# tablo_tara.net
KiCad netlist of a schematic drawn in Altium Designer
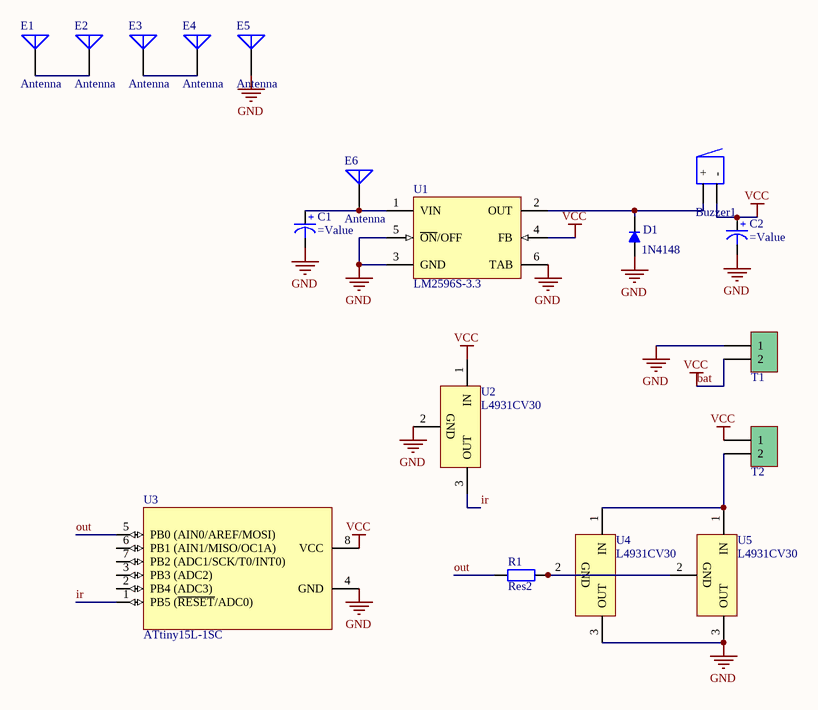
[diagram p0: tablo tara.SchDoc]

(export (version "E")
  (design (tool "Eeschema 10.0.6"))
  (components
    (comp (ref "Buzzer1")
      (value "Buzzer")
      (footprint "BUZZER")
      (fields (field (name "DESIGNER") "Seyed Mohsen Ghasemain"))
      (libsource (lib "PicPars.com_usefully_Library") (part "Buzzer"))
    )
    (comp (ref "C1")
      (value "~")
      (footprint "ELEC-CAP-RAD10-20")
      (description "Electrolytic Capacitor")
      (libsource (lib "AltiumLib1") (part "Capacitor Electrolytic"))
    )
    (comp (ref "C2")
      (value "~")
      (footprint "ELEC-CAP-RAD10-20")
      (description "Electrolytic Capacitor")
      (libsource (lib "AltiumLib1") (part "Capacitor Electrolytic"))
    )
    (comp (ref "D1")
      (value "MODEL")
      (footprint "DO-41")
      (description "Diode")
      (fields (field (name "MODEL") "1N4148"))
      (libsource (lib "AltiumLib1") (part "Diode"))
    )
    (comp (ref "E1")
      (value "Antenna")
      (footprint "PIN1")
      (description "Generic Antenna")
      (fields (field (name "PUBLISHER") "Altium Limited"))
      (libsource (lib "Miscellaneous Devices") (part "Antenna"))
    )
    (comp (ref "E2")
      (value "Antenna")
      (footprint "PIN1")
      (description "Generic Antenna")
      (fields (field (name "PUBLISHER") "Altium Limited"))
      (libsource (lib "Miscellaneous Devices") (part "Antenna"))
    )
    (comp (ref "E3")
      (value "Antenna")
      (footprint "PIN1")
      (description "Generic Antenna")
      (fields (field (name "PUBLISHER") "Altium Limited"))
      (libsource (lib "Miscellaneous Devices") (part "Antenna"))
    )
    (comp (ref "E4")
      (value "Antenna")
      (footprint "PIN1")
      (description "Generic Antenna")
      (fields (field (name "PUBLISHER") "Altium Limited"))
      (libsource (lib "Miscellaneous Devices") (part "Antenna"))
    )
    (comp (ref "E5")
      (value "Antenna")
      (footprint "PIN1")
      (description "Generic Antenna")
      (fields (field (name "PUBLISHER") "Altium Limited"))
      (libsource (lib "Miscellaneous Devices") (part "Antenna"))
    )
    (comp (ref "E6")
      (value "Antenna")
      (footprint "PIN1")
      (description "Generic Antenna")
      (fields (field (name "PUBLISHER") "Altium Limited"))
      (libsource (lib "Miscellaneous Devices") (part "Antenna"))
    )
    (comp (ref "R1")
      (value "Res2")
      (footprint "Res50")
      (description "Resistor")
      (fields (field (name "PUBLISHER") "Altium Limited"))
      (libsource (lib "Miscellaneous Devices") (part "Res50"))
    )
    (comp (ref "T1")
      (value "Phoenix terminal")
      (footprint "phoenix terminal 2")
      (description "Terminal 2 Pin")
      (fields (field (name "DESIGNER") "Seyed Mohsen Ghasemain") (field (name "E-MAIL") "picpars@gmail.com"))
      (libsource (lib "PicPars.com_usefully_Library") (part "Phoenix terminal 2"))
    )
    (comp (ref "T2")
      (value "Phoenix terminal")
      (footprint "phoenix terminal 2")
      (description "Terminal 2 Pin")
      (fields (field (name "DESIGNER") "Seyed Mohsen Ghasemain") (field (name "E-MAIL") "picpars@gmail.com"))
      (libsource (lib "PicPars.com_usefully_Library") (part "Phoenix terminal 2"))
    )
    (comp (ref "U1")
      (value "LM2596S-3.3")
      (footprint "TS5B_N")
      (description "SIMPLE SWITCHER Power Converter 150 KHz 3A Step-Down Voltage Regulator")
      (fields
        (field (name "MANUFACTURER") "National Semiconductor")
        (field (name "DIGIKEYPARTNUMBER") "LM2596S-3.3-ND")
        (field (name "PUBLISHER") "Altium Limited")
      )
      (libsource (lib "NSC Switcher") (part "LM2596S-3.3"))
    )
    (comp (ref "U2")
      (value "L4931CV30")
      (footprint "TO-220A")
      (description "250mA, Very Low Drop ( 0.4V) Voltage Regulator")
      (fields (field (name "PUBLISHER") "Altium Limited"))
      (libsource (lib "ST Power Mgt Voltage Regulator") (part "L4931CV30"))
    )
    (comp (ref "U3")
      (value "ATtiny15L-1SC")
      (footprint "8S2_N")
      (description "8-Bit AVR Microcontroller with 1K Byte of Flash Memory")
      (fields (field (name "PUBLISHER") "Altium Limited"))
      (libsource (lib "Atmel Microcontroller 8-Bit AVR") (part "ATtiny15L-1SC"))
    )
    (comp (ref "U4")
      (value "L4931CV30")
      (footprint "TO-220A")
      (description "250mA, Very Low Drop ( 0.4V) Voltage Regulator")
      (fields (field (name "PUBLISHER") "Altium Limited"))
      (libsource (lib "ST Power Mgt Voltage Regulator") (part "L4931CV30"))
    )
    (comp (ref "U5")
      (value "L4931CV30")
      (footprint "TO-220A")
      (description "250mA, Very Low Drop ( 0.4V) Voltage Regulator")
      (fields (field (name "PUBLISHER") "Altium Limited"))
      (libsource (lib "ST Power Mgt Voltage Regulator") (part "L4931CV30"))
    )
  )
  (nets
    (net (code "1") (name "/ir") (class "Default")
      (node (ref "U2") (pin "3") (pinfunction "OUT_3") (pintype "power_in"))
      (node (ref "U3") (pin "1") (pinfunction "PB5_(~{RESET}/ADC0)_1") (pintype "bidirectional"))
    )
    (net (code "2") (name "/out") (class "Default")
      (node (ref "R1") (pin "1") (pinfunction "1_1") (pintype "passive"))
      (node (ref "U3") (pin "5") (pinfunction "PB0_(AIN0/AREF/MOSI)_5") (pintype "bidirectional"))
    )
    (net (code "3") (name "GND") (class "Default")
      (node (ref "C1") (pin "1") (pinfunction "-_1") (pintype "passive"))
      (node (ref "C2") (pin "1") (pinfunction "-_1") (pintype "passive"))
      (node (ref "D1") (pin "1") (pinfunction "A_1") (pintype "passive"))
      (node (ref "E5") (pin "1") (pinfunction "A_1") (pintype "passive"))
      (node (ref "T1") (pin "1") (pinfunction "1_1") (pintype "passive"))
      (node (ref "U1") (pin "3") (pinfunction "GND_3") (pintype "power_in"))
      (node (ref "U1") (pin "5") (pinfunction "~{ON}/OFF_5") (pintype "input"))
      (node (ref "U1") (pin "6") (pinfunction "TAB_6") (pintype "power_in"))
      (node (ref "U2") (pin "2") (pinfunction "GND_2") (pintype "power_in"))
      (node (ref "U3") (pin "4") (pinfunction "GND_4") (pintype "power_in"))
      (node (ref "U4") (pin "3") (pinfunction "OUT_3") (pintype "power_in"))
      (node (ref "U5") (pin "3") (pinfunction "OUT_3") (pintype "power_in"))
    )
    (net (code "4") (name "Net-(Buzzer1-+)") (class "Default")
      (node (ref "Buzzer1") (pin "1") (pinfunction "+_1") (pintype "passive"))
      (node (ref "D1") (pin "2") (pinfunction "K_2") (pintype "passive"))
      (node (ref "U1") (pin "2") (pinfunction "OUT_2") (pintype "power_in"))
    )
    (net (code "5") (name "Net-(C1-+)") (class "Default")
      (node (ref "C1") (pin "2") (pinfunction "+_2") (pintype "passive"))
      (node (ref "E6") (pin "1") (pinfunction "A_1") (pintype "passive"))
      (node (ref "U1") (pin "1") (pinfunction "VIN_1") (pintype "power_in"))
    )
    (net (code "6") (name "Net-(E1-A)") (class "Default")
      (node (ref "E1") (pin "1") (pinfunction "A_1") (pintype "passive"))
      (node (ref "E2") (pin "1") (pinfunction "A_1") (pintype "passive"))
    )
    (net (code "7") (name "Net-(E3-A)") (class "Default")
      (node (ref "E3") (pin "1") (pinfunction "A_1") (pintype "passive"))
      (node (ref "E4") (pin "1") (pinfunction "A_1") (pintype "passive"))
    )
    (net (code "8") (name "Net-(U4-GND)") (class "Default")
      (node (ref "R1") (pin "2") (pinfunction "2_2") (pintype "passive"))
      (node (ref "U4") (pin "2") (pinfunction "GND_2") (pintype "power_in"))
      (node (ref "U5") (pin "2") (pinfunction "GND_2") (pintype "power_in"))
    )
    (net (code "9") (name "Net-(U4-IN)") (class "Default")
      (node (ref "T2") (pin "2") (pinfunction "2_2") (pintype "passive"))
      (node (ref "U4") (pin "1") (pinfunction "IN_1") (pintype "power_in"))
      (node (ref "U5") (pin "1") (pinfunction "IN_1") (pintype "power_in"))
    )
    (net (code "10") (name "VCC") (class "Default")
      (node (ref "Buzzer1") (pin "2") (pinfunction "-_2") (pintype "passive"))
      (node (ref "C2") (pin "2") (pinfunction "+_2") (pintype "passive"))
      (node (ref "T1") (pin "2") (pinfunction "2_2") (pintype "passive"))
      (node (ref "T2") (pin "1") (pinfunction "1_1") (pintype "passive"))
      (node (ref "U1") (pin "4") (pinfunction "FB_4") (pintype "input"))
      (node (ref "U2") (pin "1") (pinfunction "IN_1") (pintype "power_in"))
      (node (ref "U3") (pin "8") (pinfunction "VCC_8") (pintype "power_in"))
    )
    (net (code "11") (name "unconnected-(U3-PB1_(AIN1{slash}MISO{slash}OC1A)-Pad6)") (class "Default")
      (node (ref "U3") (pin "6") (pinfunction "PB1_(AIN1/MISO/OC1A)_6") (pintype "bidirectional"))
    )
    (net (code "12") (name "unconnected-(U3-PB2_(ADC1{slash}SCK{slash}T0{slash}INT0)-Pad7)") (class "Default")
      (node (ref "U3") (pin "7") (pinfunction "PB2_(ADC1/SCK/T0/INT0)_7") (pintype "bidirectional"))
    )
    (net (code "13") (name "unconnected-(U3-PB3_(ADC2)-Pad3)") (class "Default")
      (node (ref "U3") (pin "3") (pinfunction "PB3_(ADC2)_3") (pintype "bidirectional"))
    )
    (net (code "14") (name "unconnected-(U3-PB4_(ADC3)-Pad2)") (class "Default")
      (node (ref "U3") (pin "2") (pinfunction "PB4_(ADC3)_2") (pintype "bidirectional"))
    )
  )
)
